# dianshe1yuanli.net
KiCad netlist of a schematic drawn in Altium Designer
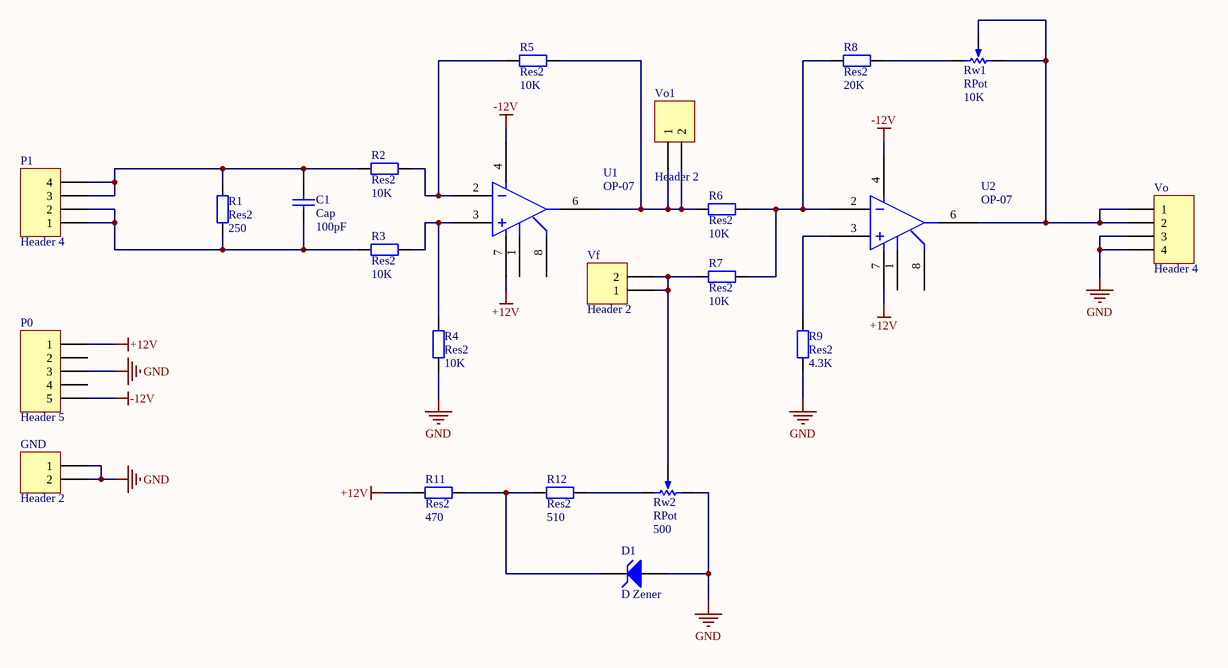
[diagram p0: dianshe1yuanli.SchDoc]

(export (version "E")
  (design (tool "Eeschema 10.0.6"))
  (components
    (comp (ref "C1")
      (value "Cap")
      (footprint "RAD0.2")
      (description "Capacitor")
      (fields (field (name "ALTIUM_VALUE") "100pF") (field (name "PUBLISHER") "Altium Limited"))
      (libsource (lib "Miscellaneous Devices") (part "Cap"))
    )
    (comp (ref "D1")
      (value "D Zener")
      (footprint "DIODE0.4")
      (description "Zener Diode")
      (fields (field (name "PUBLISHER") "Altium Limited"))
      (libsource (lib "Miscellaneous Devices") (part "D Zener"))
    )
    (comp (ref "GND")
      (value "Header 2")
      (footprint "SIP2")
      (description "Header, 2-Pin")
      (fields (field (name "PUBLISHER") "Altium Limited"))
      (libsource (lib "") (part "Header 2_2"))
    )
    (comp (ref "P0")
      (value "Header 5")
      (footprint "POWER PLUG5")
      (description "Header, 5-Pin")
      (fields (field (name "PUBLISHER") "Altium Limited"))
      (libsource (lib "Miscellaneous Connectors") (part "Header 5"))
    )
    (comp (ref "P1")
      (value "Header 4")
      (footprint "SIP4")
      (description "Header, 4-Pin")
      (fields (field (name "PUBLISHER") "Altium Limited"))
      (libsource (lib "Miscellaneous Connectors") (part "Header 4"))
    )
    (comp (ref "R1")
      (value "Res2")
      (footprint "AXIAL-0.4")
      (description "Resistor")
      (fields (field (name "ALTIUM_VALUE") "250") (field (name "PUBLISHER") "Altium Limited"))
      (libsource (lib "") (part "Res2_1"))
    )
    (comp (ref "R2")
      (value "Res2")
      (footprint "AXIAL-0.4")
      (description "Resistor")
      (fields (field (name "ALTIUM_VALUE") "10K") (field (name "PUBLISHER") "Altium Limited"))
      (libsource (lib "") (part "Res2_1"))
    )
    (comp (ref "R3")
      (value "Res2")
      (footprint "AXIAL-0.4")
      (description "Resistor")
      (fields (field (name "ALTIUM_VALUE") "10K") (field (name "PUBLISHER") "Altium Limited"))
      (libsource (lib "") (part "Res2_1"))
    )
    (comp (ref "R4")
      (value "Res2")
      (footprint "AXIAL-0.4")
      (description "Resistor")
      (fields (field (name "ALTIUM_VALUE") "10K") (field (name "PUBLISHER") "Altium Limited"))
      (libsource (lib "Miscellaneous Devices") (part "Res2"))
    )
    (comp (ref "R5")
      (value "Res2")
      (footprint "AXIAL-0.4")
      (description "Resistor")
      (fields (field (name "ALTIUM_VALUE") "10K") (field (name "PUBLISHER") "Altium Limited"))
      (libsource (lib "") (part "Res2_1"))
    )
    (comp (ref "R6")
      (value "Res2")
      (footprint "AXIAL-0.4")
      (description "Resistor")
      (fields (field (name "ALTIUM_VALUE") "10K") (field (name "PUBLISHER") "Altium Limited"))
      (libsource (lib "") (part "Res2_1"))
    )
    (comp (ref "R7")
      (value "Res2")
      (footprint "AXIAL-0.4")
      (description "Resistor")
      (fields (field (name "ALTIUM_VALUE") "10K") (field (name "PUBLISHER") "Altium Limited"))
      (libsource (lib "") (part "Res2_1"))
    )
    (comp (ref "R8")
      (value "Res2")
      (footprint "AXIAL-0.4")
      (description "Resistor")
      (fields (field (name "ALTIUM_VALUE") "20K") (field (name "PUBLISHER") "Altium Limited"))
      (libsource (lib "") (part "Res2_1"))
    )
    (comp (ref "R9")
      (value "Res2")
      (footprint "AXIAL-0.4")
      (description "Resistor")
      (fields (field (name "ALTIUM_VALUE") "4.3K") (field (name "PUBLISHER") "Altium Limited"))
      (libsource (lib "Miscellaneous Devices") (part "Res2"))
    )
    (comp (ref "R11")
      (value "Res2")
      (footprint "AXIAL-0.4")
      (description "Resistor")
      (fields (field (name "ALTIUM_VALUE") "470") (field (name "PUBLISHER") "Altium Limited"))
      (libsource (lib "") (part "Res2_1"))
    )
    (comp (ref "R12")
      (value "Res2")
      (footprint "AXIAL-0.4")
      (description "Resistor")
      (fields (field (name "ALTIUM_VALUE") "510") (field (name "PUBLISHER") "Altium Limited"))
      (libsource (lib "") (part "Res2_1"))
    )
    (comp (ref "Rw1")
      (value "RPot")
      (footprint "VR5")
      (description "Potentiometer")
      (fields (field (name "ALTIUM_VALUE") "10K") (field (name "PUBLISHER") "Altium Limited"))
      (libsource (lib "Miscellaneous Devices") (part "RPot"))
    )
    (comp (ref "Rw2")
      (value "RPot")
      (footprint "VR5")
      (description "Potentiometer")
      (fields (field (name "ALTIUM_VALUE") "500") (field (name "PUBLISHER") "Altium Limited"))
      (libsource (lib "Miscellaneous Devices") (part "RPot"))
    )
    (comp (ref "U1")
      (value "OP-07")
      (footprint "DIP-8")
      (libsource (lib "Schematic Operational Amplifiers") (part "OP-07"))
    )
    (comp (ref "U2")
      (value "OP-07")
      (footprint "DIP-8")
      (libsource (lib "Schematic Operational Amplifiers") (part "OP-07"))
    )
    (comp (ref "Vf")
      (value "Header 2")
      (footprint "SIP2")
      (description "Header, 2-Pin")
      (fields (field (name "PUBLISHER") "Altium Limited"))
      (libsource (lib "") (part "Header 2_1"))
    )
    (comp (ref "Vo")
      (value "Header 4")
      (footprint "SIP4")
      (description "Header, 4-Pin")
      (fields (field (name "PUBLISHER") "Altium Limited"))
      (libsource (lib "") (part "Header 4_1"))
    )
    (comp (ref "Vo1")
      (value "Header 2")
      (footprint "SIP2")
      (description "Header, 2-Pin")
      (fields (field (name "PUBLISHER") "Altium Limited"))
      (libsource (lib "Miscellaneous Connectors") (part "Header 2"))
    )
  )
  (nets
    (net (code "1") (name "+12V") (class "Default")
      (node (ref "P0") (pin "1") (pinfunction "1_1") (pintype "passive"))
      (node (ref "R11") (pin "1") (pinfunction "1_1") (pintype "passive"))
      (node (ref "U1") (pin "7") (pintype "passive"))
      (node (ref "U2") (pin "7") (pintype "passive"))
    )
    (net (code "2") (name "-12V") (class "Default")
      (node (ref "P0") (pin "5") (pinfunction "5_5") (pintype "passive"))
      (node (ref "U1") (pin "4") (pintype "passive"))
      (node (ref "U2") (pin "4") (pintype "passive"))
    )
    (net (code "3") (name "GND") (class "Default")
      (node (ref "D1") (pin "1") (pinfunction "A_1") (pintype "passive"))
      (node (ref "GND") (pin "1") (pinfunction "1_1") (pintype "passive"))
      (node (ref "GND") (pin "2") (pinfunction "2_2") (pintype "passive"))
      (node (ref "P0") (pin "3") (pinfunction "3_3") (pintype "passive"))
      (node (ref "R4") (pin "1") (pinfunction "1_1") (pintype "passive"))
      (node (ref "R9") (pin "1") (pinfunction "1_1") (pintype "passive"))
      (node (ref "Rw2") (pin "1") (pinfunction "TOP_1") (pintype "passive"))
      (node (ref "Vo") (pin "3") (pinfunction "3_3") (pintype "passive"))
      (node (ref "Vo") (pin "4") (pinfunction "4_4") (pintype "passive"))
    )
    (net (code "4") (name "Net-(C1-Pad1)") (class "Default")
      (node (ref "C1") (pin "1") (pinfunction "1_1") (pintype "passive"))
      (node (ref "P1") (pin "1") (pinfunction "1_1") (pintype "passive"))
      (node (ref "P1") (pin "2") (pinfunction "2_2") (pintype "passive"))
      (node (ref "R1") (pin "1") (pinfunction "1_1") (pintype "passive"))
      (node (ref "R3") (pin "1") (pinfunction "1_1") (pintype "passive"))
    )
    (net (code "5") (name "Net-(C1-Pad2)") (class "Default")
      (node (ref "C1") (pin "2") (pinfunction "2_2") (pintype "passive"))
      (node (ref "P1") (pin "3") (pinfunction "3_3") (pintype "passive"))
      (node (ref "P1") (pin "4") (pinfunction "4_4") (pintype "passive"))
      (node (ref "R1") (pin "2") (pinfunction "2_2") (pintype "passive"))
      (node (ref "R2") (pin "1") (pinfunction "1_1") (pintype "passive"))
    )
    (net (code "6") (name "Net-(D1-K)") (class "Default")
      (node (ref "D1") (pin "2") (pinfunction "K_2") (pintype "passive"))
      (node (ref "R11") (pin "2") (pinfunction "2_2") (pintype "passive"))
      (node (ref "R12") (pin "1") (pinfunction "1_1") (pintype "passive"))
    )
    (net (code "7") (name "Net-(R2-Pad2)") (class "Default")
      (node (ref "R2") (pin "2") (pinfunction "2_2") (pintype "passive"))
      (node (ref "R5") (pin "1") (pinfunction "1_1") (pintype "passive"))
      (node (ref "U1") (pin "2") (pintype "passive"))
    )
    (net (code "8") (name "Net-(R3-Pad2)") (class "Default")
      (node (ref "R3") (pin "2") (pinfunction "2_2") (pintype "passive"))
      (node (ref "R4") (pin "2") (pinfunction "2_2") (pintype "passive"))
      (node (ref "U1") (pin "3") (pintype "passive"))
    )
    (net (code "9") (name "Net-(R5-Pad2)") (class "Default")
      (node (ref "R5") (pin "2") (pinfunction "2_2") (pintype "passive"))
      (node (ref "R6") (pin "1") (pinfunction "1_1") (pintype "passive"))
      (node (ref "U1") (pin "6") (pintype "passive"))
      (node (ref "Vo1") (pin "1") (pinfunction "1_1") (pintype "passive"))
      (node (ref "Vo1") (pin "2") (pinfunction "2_2") (pintype "passive"))
    )
    (net (code "10") (name "Net-(R6-Pad2)") (class "Default")
      (node (ref "R6") (pin "2") (pinfunction "2_2") (pintype "passive"))
      (node (ref "R7") (pin "2") (pinfunction "2_2") (pintype "passive"))
      (node (ref "R8") (pin "1") (pinfunction "1_1") (pintype "passive"))
      (node (ref "U2") (pin "2") (pintype "passive"))
    )
    (net (code "11") (name "Net-(R9-Pad2)") (class "Default")
      (node (ref "R9") (pin "2") (pinfunction "2_2") (pintype "passive"))
      (node (ref "U2") (pin "3") (pintype "passive"))
    )
    (net (code "12") (name "Net-(Rw1-BOT)") (class "Default")
      (node (ref "R8") (pin "2") (pinfunction "2_2") (pintype "passive"))
      (node (ref "Rw1") (pin "3") (pinfunction "BOT_3") (pintype "passive"))
    )
    (net (code "13") (name "Net-(Rw1-TAP)") (class "Default")
      (node (ref "Rw1") (pin "1") (pinfunction "TOP_1") (pintype "passive"))
      (node (ref "Rw1") (pin "2") (pinfunction "TAP_2") (pintype "passive"))
      (node (ref "U2") (pin "6") (pintype "passive"))
      (node (ref "Vo") (pin "1") (pinfunction "1_1") (pintype "passive"))
      (node (ref "Vo") (pin "2") (pinfunction "2_2") (pintype "passive"))
    )
    (net (code "14") (name "Net-(Rw2-BOT)") (class "Default")
      (node (ref "R12") (pin "2") (pinfunction "2_2") (pintype "passive"))
      (node (ref "Rw2") (pin "3") (pinfunction "BOT_3") (pintype "passive"))
    )
    (net (code "15") (name "Net-(Rw2-TAP)") (class "Default")
      (node (ref "R7") (pin "1") (pinfunction "1_1") (pintype "passive"))
      (node (ref "Rw2") (pin "2") (pinfunction "TAP_2") (pintype "passive"))
      (node (ref "Vf") (pin "1") (pinfunction "1_1") (pintype "passive"))
      (node (ref "Vf") (pin "2") (pinfunction "2_2") (pintype "passive"))
    )
    (net (code "16") (name "unconnected-(P0-Pad2)") (class "Default")
      (node (ref "P0") (pin "2") (pinfunction "2_2") (pintype "passive"))
    )
    (net (code "17") (name "unconnected-(P0-Pad4)") (class "Default")
      (node (ref "P0") (pin "4") (pinfunction "4_4") (pintype "passive"))
    )
    (net (code "18") (name "unconnected-(U1-Pad1)") (class "Default")
      (node (ref "U1") (pin "1") (pintype "passive"))
    )
    (net (code "19") (name "unconnected-(U1-Pad8)") (class "Default")
      (node (ref "U1") (pin "8") (pintype "passive"))
    )
    (net (code "20") (name "unconnected-(U2-Pad1)") (class "Default")
      (node (ref "U2") (pin "1") (pintype "passive"))
    )
    (net (code "21") (name "unconnected-(U2-Pad8)") (class "Default")
      (node (ref "U2") (pin "8") (pintype "passive"))
    )
  )
)
